# massmfg_tinyx4_v1_1.net
KiCad netlist of a schematic drawn in EAGLE
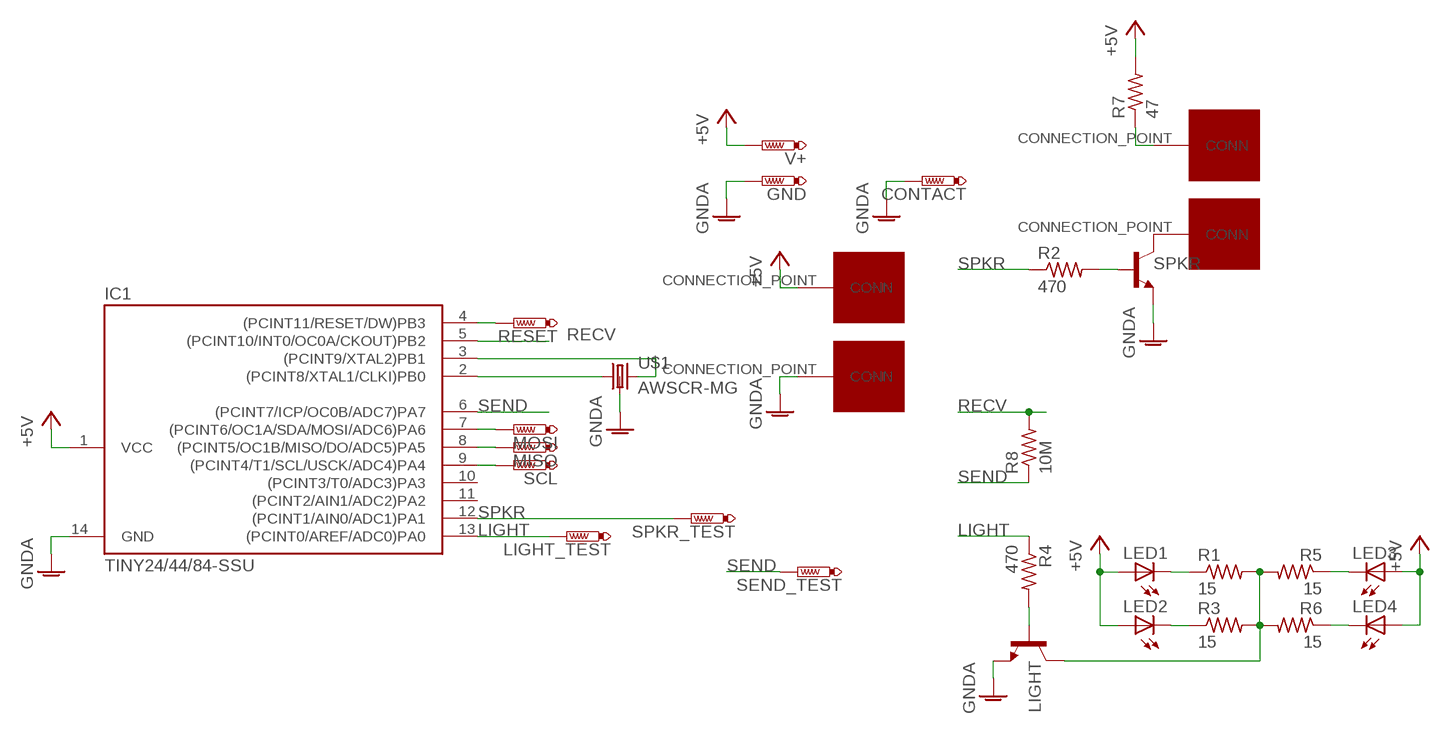
[diagram p0: schematic, sheet 1]

(export (version "E")
  (design (tool "Eeschema 10.0.6"))
  (components
    (comp (ref "CONTACT")
      (value "PTR1")
      (footprint "eagle-import:P1-06")
      (libsource (lib "eagle-import") (part "PTR1"))
    )
    (comp (ref "GND")
      (value "PTR1")
      (footprint "eagle-import:P1-06")
      (libsource (lib "eagle-import") (part "PTR1"))
    )
    (comp (ref "IC1")
      (value "TINY24/44/84-SSU")
      (footprint "eagle-import:SOIC14")
      (libsource (lib "eagle-import") (part "TINY24/44/84-SSU"))
    )
    (comp (ref "LED1")
      (value "LEDOPTEK-DURIS5")
      (footprint "eagle-import:OPTEK-DURIS5")
      (libsource (lib "eagle-import") (part "LEDOPTEK-DURIS5"))
    )
    (comp (ref "LED2")
      (value "LEDOPTEK-DURIS5")
      (footprint "eagle-import:OPTEK-DURIS5")
      (libsource (lib "eagle-import") (part "LEDOPTEK-DURIS5"))
    )
    (comp (ref "LED3")
      (value "LEDOPTEK-DURIS5")
      (footprint "eagle-import:OPTEK-DURIS5")
      (libsource (lib "eagle-import") (part "LEDOPTEK-DURIS5"))
    )
    (comp (ref "LED4")
      (value "LEDOPTEK-DURIS5")
      (footprint "eagle-import:OPTEK-DURIS5")
      (libsource (lib "eagle-import") (part "LEDOPTEK-DURIS5"))
    )
    (comp (ref "LIGHT")
      (value "SOT23-BEC")
      (footprint "eagle-import:SOT23-BEC")
      (libsource (lib "eagle-import") (part "SOT23-BEC"))
    )
    (comp (ref "LIGHT_TEST")
      (value "PTR1")
      (footprint "eagle-import:P1-06")
      (libsource (lib "eagle-import") (part "PTR1"))
    )
    (comp (ref "MISO")
      (value "PTR1")
      (footprint "eagle-import:P1-06")
      (libsource (lib "eagle-import") (part "PTR1"))
    )
    (comp (ref "MOSI")
      (value "PTR1")
      (footprint "eagle-import:P1-06")
      (libsource (lib "eagle-import") (part "PTR1"))
    )
    (comp (ref "R1")
      (value "15")
      (footprint "eagle-import:M1206")
      (libsource (lib "eagle-import") (part "R-US_M1206"))
    )
    (comp (ref "R2")
      (value "470")
      (footprint "eagle-import:R0805")
      (libsource (lib "eagle-import") (part "R-US_R0805"))
    )
    (comp (ref "R3")
      (value "15")
      (footprint "eagle-import:M1206")
      (libsource (lib "eagle-import") (part "R-US_M1206"))
    )
    (comp (ref "R4")
      (value "470")
      (footprint "eagle-import:R0805")
      (libsource (lib "eagle-import") (part "R-US_R0805"))
    )
    (comp (ref "R5")
      (value "15")
      (footprint "eagle-import:M1206")
      (libsource (lib "eagle-import") (part "R-US_M1206"))
    )
    (comp (ref "R6")
      (value "15")
      (footprint "eagle-import:M1206")
      (libsource (lib "eagle-import") (part "R-US_M1206"))
    )
    (comp (ref "R7")
      (value "47")
      (footprint "eagle-import:M1206")
      (libsource (lib "eagle-import") (part "R-US_M1206"))
    )
    (comp (ref "R8")
      (value "10M")
      (footprint "eagle-import:M1206")
      (libsource (lib "eagle-import") (part "R-US_M1206"))
    )
    (comp (ref "RESET")
      (value "PTR1")
      (footprint "eagle-import:P1-06")
      (libsource (lib "eagle-import") (part "PTR1"))
    )
    (comp (ref "SCL")
      (value "PTR1")
      (footprint "eagle-import:P1-06")
      (libsource (lib "eagle-import") (part "PTR1"))
    )
    (comp (ref "SEND_TEST")
      (value "PTR1")
      (footprint "eagle-import:P1-06")
      (libsource (lib "eagle-import") (part "PTR1"))
    )
    (comp (ref "SPEAKER_PLUS")
      (value "CONNECTION_POINT")
      (footprint "eagle-import:10X3_CONNECTION_POINT")
      (libsource (lib "eagle-import") (part "CONNECTION_POINT"))
    )
    (comp (ref "SPKR")
      (value "SOT23-BEC")
      (footprint "eagle-import:SOT23-BEC")
      (libsource (lib "eagle-import") (part "SOT23-BEC"))
    )
    (comp (ref "SPKR_MINUS")
      (value "CONNECTION_POINT")
      (footprint "eagle-import:10X3_CONNECTION_POINT")
      (libsource (lib "eagle-import") (part "CONNECTION_POINT"))
    )
    (comp (ref "SPKR_TEST")
      (value "PTR1")
      (footprint "eagle-import:P1-06")
      (libsource (lib "eagle-import") (part "PTR1"))
    )
    (comp (ref "U$1")
      (value "AWSCR-MG")
      (footprint "eagle-import:AWSCR-MG")
      (libsource (lib "eagle-import") (part "AWSCR-MG"))
    )
    (comp (ref "U$3")
      (value "CONNECTION_POINT")
      (footprint "eagle-import:10X3_CONNECTION_POINT")
      (libsource (lib "eagle-import") (part "CONNECTION_POINT"))
    )
    (comp (ref "U$5")
      (value "CONNECTION_POINT")
      (footprint "eagle-import:10X3_CONNECTION_POINT")
      (libsource (lib "eagle-import") (part "CONNECTION_POINT"))
    )
    (comp (ref "V+")
      (value "PTR1")
      (footprint "eagle-import:P1-06")
      (libsource (lib "eagle-import") (part "PTR1"))
    )
  )
  (nets
    (net (code "1") (name "+5V") (class "Default")
      (node (ref "IC1") (pin "1") (pinfunction "VCC_1") (pintype "power_in"))
      (node (ref "LED1") (pin "ANODE") (pinfunction "A_ANODE") (pintype "passive"))
      (node (ref "LED2") (pin "ANODE") (pinfunction "A_ANODE") (pintype "passive"))
      (node (ref "LED3") (pin "ANODE") (pinfunction "A_ANODE") (pintype "passive"))
      (node (ref "LED4") (pin "ANODE") (pinfunction "A_ANODE") (pintype "passive"))
      (node (ref "R7") (pin "2") (pinfunction "2_2") (pintype "passive"))
      (node (ref "U$3") (pin "CONNECTION_POINT") (pinfunction "CONN_CONNECTION_POINT") (pintype "bidirectional"))
      (node (ref "V+") (pin "TP") (pinfunction "TP_TP") (pintype "input"))
    )
    (net (code "2") (name "/LIGHT") (class "Default")
      (node (ref "IC1") (pin "13") (pinfunction "(PCINT0/AREF/ADC0)PA0_13") (pintype "bidirectional"))
      (node (ref "LIGHT_TEST") (pin "TP") (pinfunction "TP_TP") (pintype "input"))
      (node (ref "R4") (pin "1") (pinfunction "1_1") (pintype "passive"))
    )
    (net (code "3") (name "/RECV") (class "Default")
      (node (ref "IC1") (pin "5") (pinfunction "(PCINT10/INT0/OC0A/CKOUT)PB2_5") (pintype "bidirectional"))
      (node (ref "R8") (pin "2") (pinfunction "2_2") (pintype "passive"))
    )
    (net (code "4") (name "/SEND") (class "Default")
      (node (ref "IC1") (pin "6") (pinfunction "(PCINT7/ICP/OC0B/ADC7)PA7_6") (pintype "bidirectional"))
      (node (ref "R8") (pin "1") (pinfunction "1_1") (pintype "passive"))
      (node (ref "SEND_TEST") (pin "TP") (pinfunction "TP_TP") (pintype "input"))
    )
    (net (code "5") (name "/SPKR") (class "Default")
      (node (ref "IC1") (pin "12") (pinfunction "(PCINT1/AIN0/ADC1)PA1_12") (pintype "bidirectional"))
      (node (ref "R2") (pin "1") (pinfunction "1_1") (pintype "passive"))
      (node (ref "SPKR_TEST") (pin "TP") (pinfunction "TP_TP") (pintype "input"))
    )
    (net (code "6") (name "GNDA") (class "Default")
      (node (ref "CONTACT") (pin "TP") (pinfunction "TP_TP") (pintype "input"))
      (node (ref "GND") (pin "TP") (pinfunction "TP_TP") (pintype "input"))
      (node (ref "IC1") (pin "14") (pinfunction "GND_14") (pintype "power_in"))
      (node (ref "LIGHT") (pin "E") (pinfunction "E_E") (pintype "passive"))
      (node (ref "SPKR") (pin "E") (pinfunction "E_E") (pintype "passive"))
      (node (ref "U$1") (pin "GND") (pinfunction "3_GND") (pintype "passive"))
      (node (ref "U$5") (pin "CONNECTION_POINT") (pinfunction "CONN_CONNECTION_POINT") (pintype "bidirectional"))
    )
    (net (code "7") (name "Net-(IC1-(PCINT4{slash}T1{slash}SCL{slash}USCK{slash}ADC4)PA4)") (class "Default")
      (node (ref "IC1") (pin "9") (pinfunction "(PCINT4/T1/SCL/USCK/ADC4)PA4_9") (pintype "bidirectional"))
      (node (ref "SCL") (pin "TP") (pinfunction "TP_TP") (pintype "input"))
    )
    (net (code "8") (name "Net-(IC1-(PCINT5{slash}OC1B{slash}MISO{slash}DO{slash}ADC5)PA5)") (class "Default")
      (node (ref "IC1") (pin "8") (pinfunction "(PCINT5/OC1B/MISO/DO/ADC5)PA5_8") (pintype "bidirectional"))
      (node (ref "MISO") (pin "TP") (pinfunction "TP_TP") (pintype "input"))
    )
    (net (code "9") (name "Net-(IC1-(PCINT6{slash}OC1A{slash}SDA{slash}MOSI{slash}ADC6)PA6)") (class "Default")
      (node (ref "IC1") (pin "7") (pinfunction "(PCINT6/OC1A/SDA/MOSI/ADC6)PA6_7") (pintype "bidirectional"))
      (node (ref "MOSI") (pin "TP") (pinfunction "TP_TP") (pintype "input"))
    )
    (net (code "10") (name "Net-(IC1-(PCINT8{slash}XTAL1{slash}CLKI)PB0)") (class "Default")
      (node (ref "IC1") (pin "2") (pinfunction "(PCINT8/XTAL1/CLKI)PB0_2") (pintype "bidirectional"))
      (node (ref "U$1") (pin "IN") (pinfunction "1_IN") (pintype "passive"))
    )
    (net (code "11") (name "Net-(IC1-(PCINT9{slash}XTAL2)PB1)") (class "Default")
      (node (ref "IC1") (pin "3") (pinfunction "(PCINT9/XTAL2)PB1_3") (pintype "bidirectional"))
      (node (ref "U$1") (pin "OUT") (pinfunction "2_OUT") (pintype "passive"))
    )
    (net (code "12") (name "Net-(IC1-(PCINT11{slash}RESET{slash}DW)PB3)") (class "Default")
      (node (ref "IC1") (pin "4") (pinfunction "(PCINT11/RESET/DW)PB3_4") (pintype "bidirectional"))
      (node (ref "RESET") (pin "TP") (pinfunction "TP_TP") (pintype "input"))
    )
    (net (code "13") (name "Net-(LED1-C)") (class "Default")
      (node (ref "LED1") (pin "CATHODE") (pinfunction "C_CATHODE") (pintype "passive"))
      (node (ref "R1") (pin "1") (pinfunction "1_1") (pintype "passive"))
    )
    (net (code "14") (name "Net-(LED2-C)") (class "Default")
      (node (ref "LED2") (pin "CATHODE") (pinfunction "C_CATHODE") (pintype "passive"))
      (node (ref "R3") (pin "1") (pinfunction "1_1") (pintype "passive"))
    )
    (net (code "15") (name "Net-(LED3-C)") (class "Default")
      (node (ref "LED3") (pin "CATHODE") (pinfunction "C_CATHODE") (pintype "passive"))
      (node (ref "R5") (pin "1") (pinfunction "1_1") (pintype "passive"))
    )
    (net (code "16") (name "Net-(LED4-C)") (class "Default")
      (node (ref "LED4") (pin "CATHODE") (pinfunction "C_CATHODE") (pintype "passive"))
      (node (ref "R6") (pin "1") (pinfunction "1_1") (pintype "passive"))
    )
    (net (code "17") (name "Net-(LIGHT-PadB)") (class "Default")
      (node (ref "LIGHT") (pin "B") (pinfunction "B_B") (pintype "passive"))
      (node (ref "R4") (pin "2") (pinfunction "2_2") (pintype "passive"))
    )
    (net (code "18") (name "Net-(LIGHT-PadC)") (class "Default")
      (node (ref "LIGHT") (pin "C") (pinfunction "C_C") (pintype "passive"))
      (node (ref "R1") (pin "2") (pinfunction "2_2") (pintype "passive"))
      (node (ref "R3") (pin "2") (pinfunction "2_2") (pintype "passive"))
      (node (ref "R5") (pin "2") (pinfunction "2_2") (pintype "passive"))
      (node (ref "R6") (pin "2") (pinfunction "2_2") (pintype "passive"))
    )
    (net (code "19") (name "Net-(R2-Pad2)") (class "Default")
      (node (ref "R2") (pin "2") (pinfunction "2_2") (pintype "passive"))
      (node (ref "SPKR") (pin "B") (pinfunction "B_B") (pintype "passive"))
    )
    (net (code "20") (name "Net-(SPEAKER_PLUS-CONN)") (class "Default")
      (node (ref "R7") (pin "1") (pinfunction "1_1") (pintype "passive"))
      (node (ref "SPEAKER_PLUS") (pin "CONNECTION_POINT") (pinfunction "CONN_CONNECTION_POINT") (pintype "bidirectional"))
    )
    (net (code "21") (name "Net-(SPKR_MINUS-CONN)") (class "Default")
      (node (ref "SPKR") (pin "C") (pinfunction "C_C") (pintype "passive"))
      (node (ref "SPKR_MINUS") (pin "CONNECTION_POINT") (pinfunction "CONN_CONNECTION_POINT") (pintype "bidirectional"))
    )
    (net (code "22") (name "unconnected-(IC1-(PCINT2{slash}AIN1{slash}ADC2)PA2-Pad11)") (class "Default")
      (node (ref "IC1") (pin "11") (pinfunction "(PCINT2/AIN1/ADC2)PA2_11") (pintype "bidirectional"))
    )
    (net (code "23") (name "unconnected-(IC1-(PCINT3{slash}T0{slash}ADC3)PA3-Pad10)") (class "Default")
      (node (ref "IC1") (pin "10") (pinfunction "(PCINT3/T0/ADC3)PA3_10") (pintype "bidirectional"))
    )
  )
)
